# BTS_V2.net
KiCad netlist of a schematic drawn in EAGLE
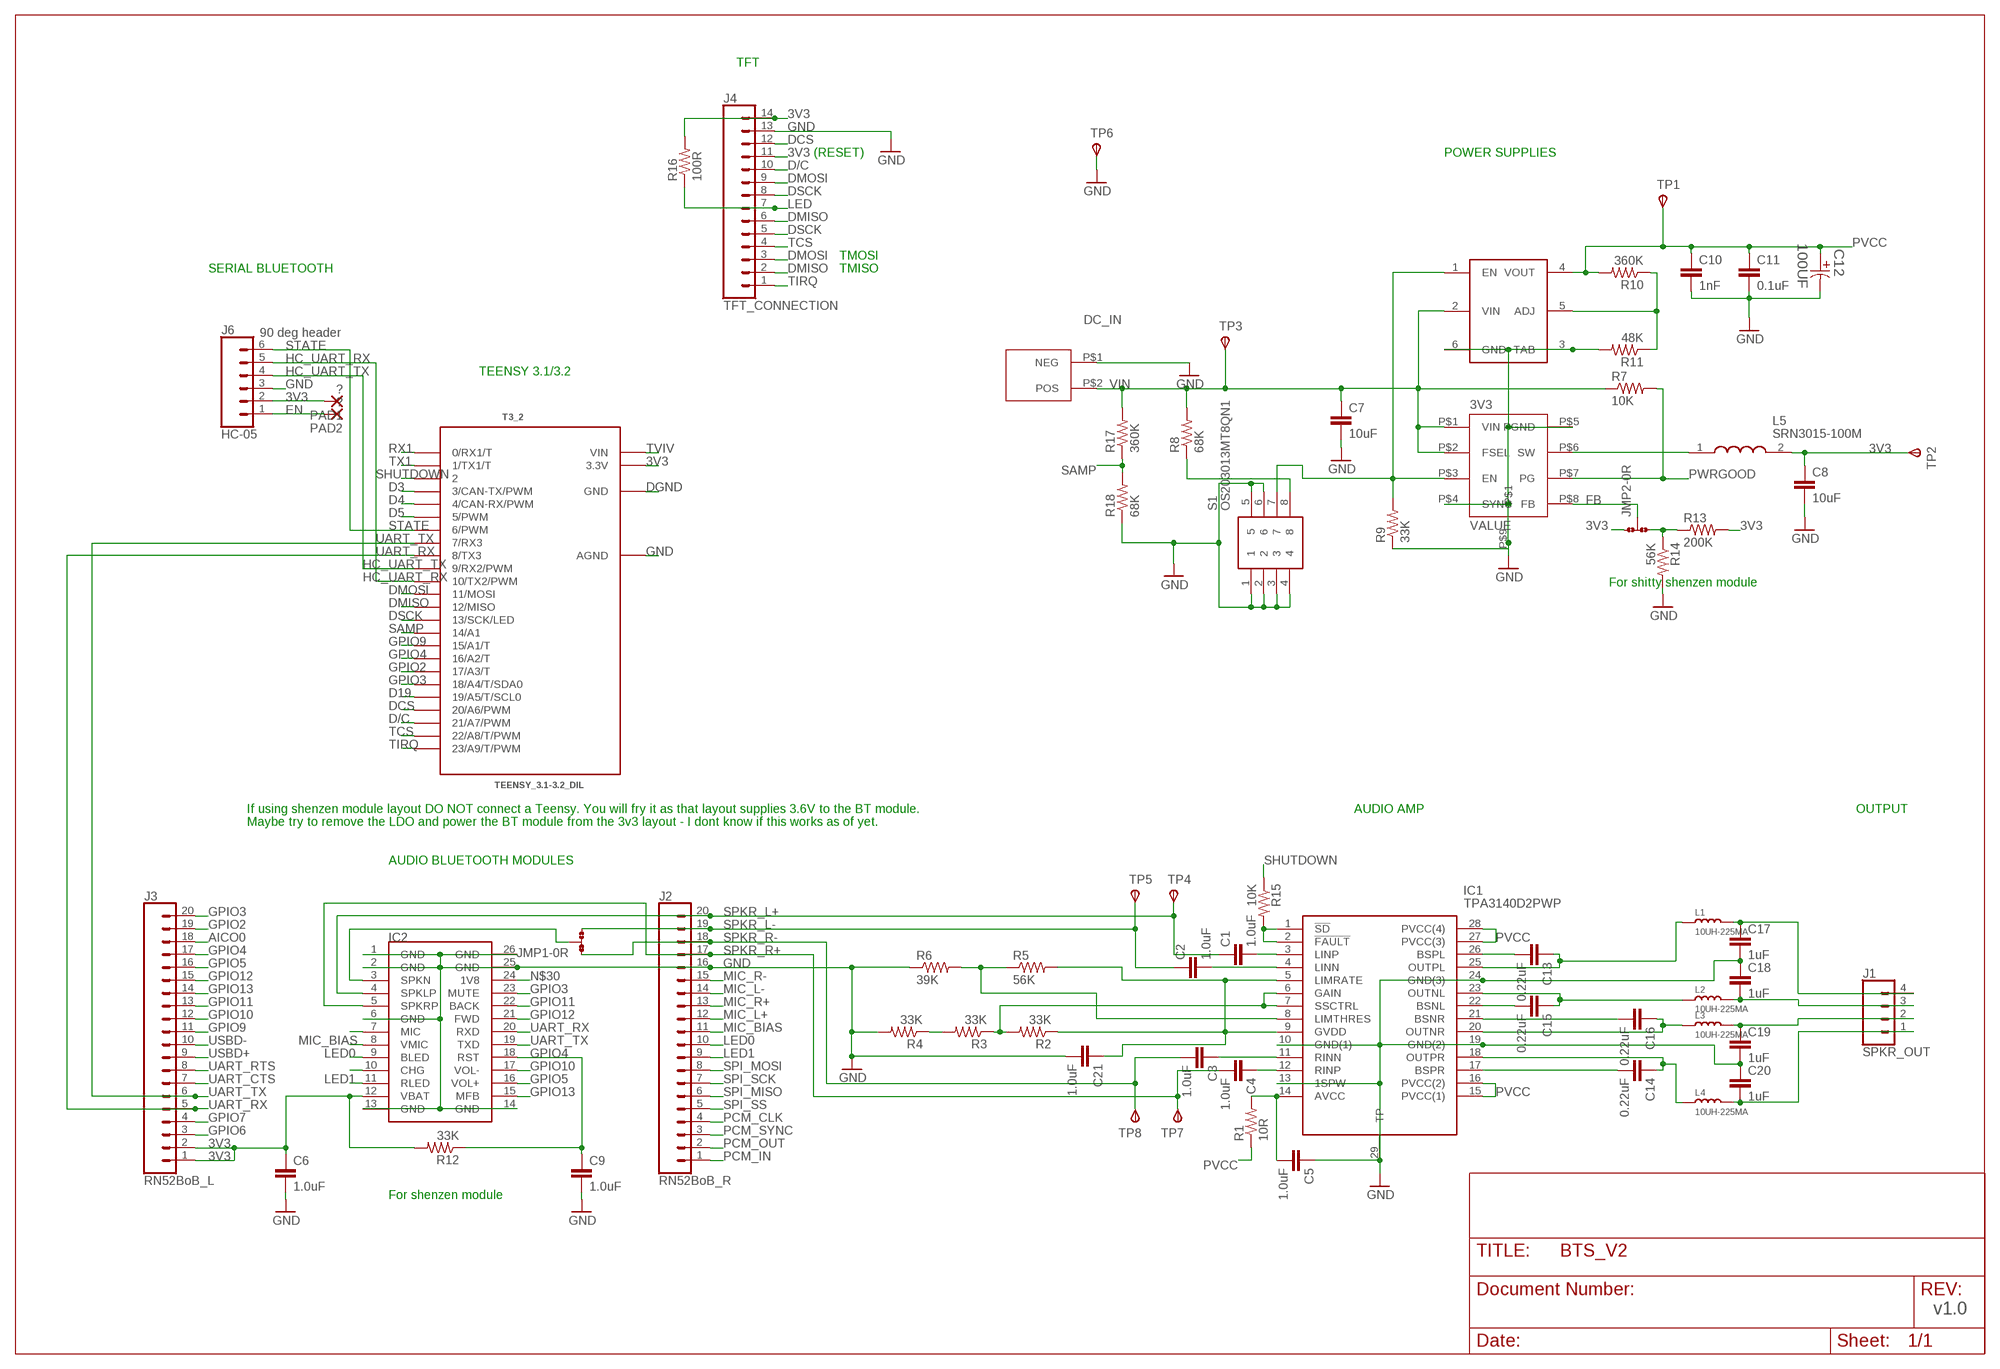
[diagram p0: schematic, sheet 1]

(export (version "E")
  (design (tool "Eeschema 10.0.6"))
  (components
    (comp (ref "3V3")
      (value "ADP2370")
      (footprint "eagle-import:3MM_LFCSP_QFN")
      (libsource (lib "eagle-import") (part "ADP2370"))
    )
    (comp (ref "C1")
      (value "1.0uF")
      (footprint "eagle-import:0603")
      (libsource (lib "eagle-import") (part "1.0UF-0603-16V-10%"))
    )
    (comp (ref "C2")
      (value "1.0uF")
      (footprint "eagle-import:0603")
      (libsource (lib "eagle-import") (part "1.0UF-0603-16V-10%"))
    )
    (comp (ref "C3")
      (value "1.0uF")
      (footprint "eagle-import:0603")
      (libsource (lib "eagle-import") (part "1.0UF-0603-16V-10%"))
    )
    (comp (ref "C4")
      (value "1.0uF")
      (footprint "eagle-import:0603")
      (libsource (lib "eagle-import") (part "1.0UF-0603-16V-10%"))
    )
    (comp (ref "C5")
      (value "1.0uF")
      (footprint "eagle-import:0603")
      (libsource (lib "eagle-import") (part "1.0UF-0603-16V-10%"))
    )
    (comp (ref "C6")
      (value "1.0uF")
      (footprint "eagle-import:0603")
      (libsource (lib "eagle-import") (part "1.0UF-0603-16V-10%"))
    )
    (comp (ref "C7")
      (value "10uF")
      (footprint "eagle-import:C3216")
      (fields (field (name "SPICEPREFIX") "10uF"))
      (libsource (lib "eagle-import") (part "C-EUC3216"))
    )
    (comp (ref "C8")
      (value "10uF")
      (footprint "eagle-import:C3216")
      (libsource (lib "eagle-import") (part "C-EUC3216"))
    )
    (comp (ref "C9")
      (value "1.0uF")
      (footprint "eagle-import:0603")
      (libsource (lib "eagle-import") (part "1.0UF-0603-16V-10%"))
    )
    (comp (ref "C10")
      (value "1nF")
      (footprint "eagle-import:0603")
      (libsource (lib "eagle-import") (part "1.0NF/1000PF-0603-50V-10%"))
    )
    (comp (ref "C11")
      (value "0.1uF")
      (footprint "eagle-import:0603")
      (libsource (lib "eagle-import") (part "0.1UF-0603-25V-(+80/-20%)"))
    )
    (comp (ref "C12")
      (value "100UF")
      (footprint "eagle-import:CAPAE660X610N")
      (fields (field (name "MPN") "EEE-FK1C101P") (field (name "TOLERANCE") "±20 %"))
      (libsource (lib "eagle-import") (part "EEE--CASE-DFK1C101P"))
    )
    (comp (ref "C13")
      (value "0.22uF")
      (footprint "eagle-import:0603")
      (libsource (lib "eagle-import") (part "0.22UF-0603-50V-(-20/+80%)"))
    )
    (comp (ref "C14")
      (value "0.22uF")
      (footprint "eagle-import:0603")
      (libsource (lib "eagle-import") (part "0.22UF-0603-50V-(-20/+80%)"))
    )
    (comp (ref "C15")
      (value "0.22uF")
      (footprint "eagle-import:0603")
      (libsource (lib "eagle-import") (part "0.22UF-0603-50V-(-20/+80%)"))
    )
    (comp (ref "C16")
      (value "0.22uF")
      (footprint "eagle-import:0603")
      (libsource (lib "eagle-import") (part "0.22UF-0603-50V-(-20/+80%)"))
    )
    (comp (ref "C17")
      (value "1uF")
      (footprint "eagle-import:0603")
      (libsource (lib "eagle-import") (part "1.0NF/1000PF-0603-50V-10%"))
    )
    (comp (ref "C18")
      (value "1uF")
      (footprint "eagle-import:0603")
      (libsource (lib "eagle-import") (part "1.0NF/1000PF-0603-50V-10%"))
    )
    (comp (ref "C19")
      (value "1uF")
      (footprint "eagle-import:0603")
      (libsource (lib "eagle-import") (part "1.0NF/1000PF-0603-50V-10%"))
    )
    (comp (ref "C20")
      (value "1uF")
      (footprint "eagle-import:0603")
      (libsource (lib "eagle-import") (part "1.0NF/1000PF-0603-50V-10%"))
    )
    (comp (ref "C21")
      (value "1.0uF")
      (footprint "eagle-import:0603")
      (libsource (lib "eagle-import") (part "1.0UF-0603-16V-10%"))
    )
    (comp (ref "IC1")
      (value "TPA3140D2PWP")
      (footprint "eagle-import:SOP65P640X120-29N")
      (libsource (lib "eagle-import") (part "TPA3140D2PWP"))
    )
    (comp (ref "IC2")
      (value "BLK-MD-SPK-B")
      (footprint "eagle-import:BLK-MD-SPK-B")
      (libsource (lib "eagle-import") (part "BLK-MD-SPK-B"))
    )
    (comp (ref "J1")
      (value "SPKR_OUT")
      (footprint "eagle-import:SCREWTERMINAL-3.5MM-4")
      (libsource (lib "eagle-import") (part "CONN_04SCREW"))
    )
    (comp (ref "J2")
      (value "RN52BoB_R")
      (footprint "eagle-import:1X20")
      (libsource (lib "eagle-import") (part "CONN_20"))
    )
    (comp (ref "J3")
      (value "RN52BoB_L")
      (footprint "eagle-import:1X20")
      (libsource (lib "eagle-import") (part "CONN_20"))
    )
    (comp (ref "J4")
      (value "TFT_CONNECTION")
      (footprint "eagle-import:1X14")
      (libsource (lib "eagle-import") (part "CONN_14"))
    )
    (comp (ref "J6")
      (value "HC-05")
      (footprint "eagle-import:1X06")
      (libsource (lib "eagle-import") (part "CONN_06SILK_FEMALE_PTH"))
    )
    (comp (ref "JMP1")
      (value "0R-JUMPA")
      (footprint "eagle-import:A0R-JMP")
      (libsource (lib "eagle-import") (part "0R-JUMPA"))
    )
    (comp (ref "JMP2")
      (value "0R-JUMPA")
      (footprint "eagle-import:A0R-JMP")
      (libsource (lib "eagle-import") (part "0R-JUMPA"))
    )
    (comp (ref "L1")
      (value "10UH-225MA")
      (footprint "eagle-import:L0806")
      (fields (field (name "MPN") "LQH2MCN100K02L"))
      (libsource (lib "eagle-import") (part "SMD-INDUCTOR-10UH-225MA-10%(0806)"))
    )
    (comp (ref "L2")
      (value "10UH-225MA")
      (footprint "eagle-import:L0806")
      (fields (field (name "MPN") "LQH2MCN100K02L"))
      (libsource (lib "eagle-import") (part "SMD-INDUCTOR-10UH-225MA-10%(0806)"))
    )
    (comp (ref "L3")
      (value "10UH-225MA")
      (footprint "eagle-import:L0806")
      (fields (field (name "MPN") "LQH2MCN100K02L"))
      (libsource (lib "eagle-import") (part "SMD-INDUCTOR-10UH-225MA-10%(0806)"))
    )
    (comp (ref "L4")
      (value "10UH-225MA")
      (footprint "eagle-import:L0806")
      (fields (field (name "MPN") "LQH2MCN100K02L"))
      (libsource (lib "eagle-import") (part "SMD-INDUCTOR-10UH-225MA-10%(0806)"))
    )
    (comp (ref "L5")
      (value "SRN3015-100M")
      (footprint "eagle-import:SRN3015")
      (fields (field (name "RS_PART_NUMBER") "7435071"))
      (libsource (lib "eagle-import") (part "SRN3015-100M"))
    )
    (comp (ref "PAD1")
      (value "?")
      (footprint "eagle-import:SMD1,27-2,54")
      (libsource (lib "eagle-import") (part "SMD2"))
    )
    (comp (ref "PAD2")
      (value "?")
      (footprint "eagle-import:SMD1,27-2,54")
      (libsource (lib "eagle-import") (part "SMD2"))
    )
    (comp (ref "R1")
      (value "10R")
      (footprint "eagle-import:R0603")
      (fields (field (name "RESISTANCE") "10R"))
      (libsource (lib "eagle-import") (part "R-US_R0603"))
    )
    (comp (ref "R2")
      (value "33K")
      (footprint "eagle-import:R0603")
      (fields (field (name "RESISTANCE") "33K"))
      (libsource (lib "eagle-import") (part "R-US_R0603"))
    )
    (comp (ref "R3")
      (value "33K")
      (footprint "eagle-import:R0603")
      (fields (field (name "RESISTANCE") "33K"))
      (libsource (lib "eagle-import") (part "R-US_R0603"))
    )
    (comp (ref "R4")
      (value "33K")
      (footprint "eagle-import:R0603")
      (fields (field (name "RESISTANCE") "33K"))
      (libsource (lib "eagle-import") (part "R-US_R0603"))
    )
    (comp (ref "R5")
      (value "56K")
      (footprint "eagle-import:R0603")
      (fields (field (name "RESISTANCE") "56K"))
      (libsource (lib "eagle-import") (part "R-US_R0603"))
    )
    (comp (ref "R6")
      (value "39K")
      (footprint "eagle-import:R0603")
      (fields (field (name "RESISTANCE") "39K"))
      (libsource (lib "eagle-import") (part "R-US_R0603"))
    )
    (comp (ref "R7")
      (value "10K")
      (footprint "eagle-import:R0603")
      (fields (field (name "RESISTANCE") "10K"))
      (libsource (lib "eagle-import") (part "R-US_R0603"))
    )
    (comp (ref "R8")
      (value "68K")
      (footprint "eagle-import:R0603")
      (fields (field (name "RESISTANCE") "68K"))
      (libsource (lib "eagle-import") (part "R-US_R0603"))
    )
    (comp (ref "R9")
      (value "33K")
      (footprint "eagle-import:R0603")
      (fields (field (name "RESISTANCE") "33K"))
      (libsource (lib "eagle-import") (part "R-US_R0603"))
    )
    (comp (ref "R10")
      (value "360K")
      (footprint "eagle-import:R0603")
      (fields (field (name "RESISTANCE") "10K"))
      (libsource (lib "eagle-import") (part "R-US_R0603"))
    )
    (comp (ref "R11")
      (value "48K")
      (footprint "eagle-import:R0603")
      (fields (field (name "RESISTANCE") "10K"))
      (libsource (lib "eagle-import") (part "R-US_R0603"))
    )
    (comp (ref "R12")
      (value "33K")
      (footprint "eagle-import:R0603")
      (fields (field (name "RESISTANCE") "33K"))
      (libsource (lib "eagle-import") (part "R-US_R0603"))
    )
    (comp (ref "R13")
      (value "200K")
      (footprint "eagle-import:R0603")
      (fields (field (name "RESISTANCE") "10K"))
      (libsource (lib "eagle-import") (part "R-US_R0603"))
    )
    (comp (ref "R14")
      (value "56K")
      (footprint "eagle-import:R0603")
      (fields (field (name "RESISTANCE") "10K"))
      (libsource (lib "eagle-import") (part "R-US_R0603"))
    )
    (comp (ref "R15")
      (value "10K")
      (footprint "eagle-import:R0603")
      (fields (field (name "RESISTANCE") "33K"))
      (libsource (lib "eagle-import") (part "R-US_R0603"))
    )
    (comp (ref "R16")
      (value "100R")
      (footprint "eagle-import:R0603")
      (libsource (lib "eagle-import") (part "R-US_R0603"))
    )
    (comp (ref "R17")
      (value "360K")
      (footprint "eagle-import:R0603")
      (fields (field (name "RESISTANCE") "68K"))
      (libsource (lib "eagle-import") (part "R-US_R0603"))
    )
    (comp (ref "R18")
      (value "68K")
      (footprint "eagle-import:R0603")
      (fields (field (name "RESISTANCE") "68K"))
      (libsource (lib "eagle-import") (part "R-US_R0603"))
    )
    (comp (ref "S1")
      (value "OS203013MT8QN1")
      (footprint "eagle-import:OS203013MT8QN1")
      (libsource (lib "eagle-import") (part "OS203013MT8QN1"))
    )
    (comp (ref "T3_2")
      (value "TEENSY_3.1-3.2_DIL")
      (footprint "eagle-import:TEENSY_3.0-3.2&LC_DIL")
      (libsource (lib "eagle-import") (part "TEENSY_3.1-3.2_DIL"))
    )
    (comp (ref "TP1")
      (value "TPSPAD1-17")
      (footprint "eagle-import:P1-17")
      (libsource (lib "eagle-import") (part "TPSPAD1-17"))
    )
    (comp (ref "TP2")
      (value "TPSPAD1-17")
      (footprint "eagle-import:P1-17")
      (libsource (lib "eagle-import") (part "TPSPAD1-17"))
    )
    (comp (ref "TP3")
      (value "TPSPAD1-17")
      (footprint "eagle-import:P1-17")
      (libsource (lib "eagle-import") (part "TPSPAD1-17"))
    )
    (comp (ref "TP4")
      (value "TPSPAD1-17")
      (footprint "eagle-import:P1-17")
      (libsource (lib "eagle-import") (part "TPSPAD1-17"))
    )
    (comp (ref "TP5")
      (value "TPSPAD1-17")
      (footprint "eagle-import:P1-17")
      (libsource (lib "eagle-import") (part "TPSPAD1-17"))
    )
    (comp (ref "TP6")
      (value "TPSPAD1-17")
      (footprint "eagle-import:P1-17")
      (libsource (lib "eagle-import") (part "TPSPAD1-17"))
    )
    (comp (ref "TP7")
      (value "TPSPAD1-17")
      (footprint "eagle-import:P1-17")
      (libsource (lib "eagle-import") (part "TPSPAD1-17"))
    )
    (comp (ref "TP8")
      (value "TPSPAD1-17")
      (footprint "eagle-import:P1-17")
      (libsource (lib "eagle-import") (part "TPSPAD1-17"))
    )
    (comp (ref "U$1")
      (value "HK_XT-60")
      (footprint "eagle-import:HOBBYKING_XT-60")
      (libsource (lib "eagle-import") (part "HK_XT-60"))
    )
    (comp (ref "U$2")
      (value "NCP59302")
      (footprint "eagle-import:D2PAK-5")
      (libsource (lib "eagle-import") (part "NCP59302"))
    )
  )
  (nets
    (net (code "1") (name "/3V3") (class "Default")
      (node (ref "C6") (pin "1") (pinfunction "1_1") (pintype "passive"))
      (node (ref "C8") (pin "1") (pinfunction "1_1") (pintype "passive"))
      (node (ref "IC2") (pin "12") (pinfunction "VBAT_12") (pintype "bidirectional"))
      (node (ref "J3") (pin "1") (pinfunction "1_1") (pintype "passive"))
      (node (ref "J3") (pin "2") (pinfunction "2_2") (pintype "passive"))
      (node (ref "J4") (pin "11") (pinfunction "11_11") (pintype "passive"))
      (node (ref "J4") (pin "14") (pinfunction "14_14") (pintype "passive"))
      (node (ref "J6") (pin "2") (pinfunction "2_2") (pintype "passive"))
      (node (ref "JMP2") (pin "1") (pinfunction "1_1") (pintype "passive"))
      (node (ref "L5") (pin "2") (pinfunction "2_2") (pintype "input"))
      (node (ref "PAD1") (pin "1") (pinfunction "P_1") (pintype "passive"))
      (node (ref "R12") (pin "2") (pinfunction "2_2") (pintype "passive"))
      (node (ref "R13") (pin "2") (pinfunction "2_2") (pintype "passive"))
      (node (ref "R16") (pin "2") (pinfunction "2_2") (pintype "passive"))
      (node (ref "T3_2") (pin "3.3V") (pinfunction "3.3V_3.3V") (pintype "power_in"))
      (node (ref "TP2") (pin "TP") (pinfunction "PP_TP") (pintype "input"))
    )
    (net (code "2") (name "/AICO0") (class "Default")
      (node (ref "J3") (pin "18") (pinfunction "18_18") (pintype "passive"))
    )
    (net (code "3") (name "/D3") (class "Default")
      (node (ref "T3_2") (pin "3") (pinfunction "3/CAN-TX/PWM_3") (pintype "bidirectional"))
    )
    (net (code "4") (name "/D4") (class "Default")
      (node (ref "T3_2") (pin "4") (pinfunction "4/CAN-RX/PWM_4") (pintype "bidirectional"))
    )
    (net (code "5") (name "/D5") (class "Default")
      (node (ref "T3_2") (pin "5") (pinfunction "5/PWM_5") (pintype "bidirectional"))
    )
    (net (code "6") (name "/D19") (class "Default")
      (node (ref "T3_2") (pin "19/A5") (pinfunction "19/A5/T/SCL0_19/A5") (pintype "bidirectional"))
    )
    (net (code "7") (name "/DCS") (class "Default")
      (node (ref "J4") (pin "12") (pinfunction "12_12") (pintype "passive"))
      (node (ref "T3_2") (pin "20/A6") (pinfunction "20/A6/PWM_20/A6") (pintype "bidirectional"))
    )
    (net (code "8") (name "/DGND") (class "Default")
      (node (ref "T3_2") (pin "GND") (pinfunction "GND_GND") (pintype "power_in"))
    )
    (net (code "9") (name "/DMISO") (class "Default")
      (node (ref "J4") (pin "2") (pinfunction "2_2") (pintype "passive"))
      (node (ref "J4") (pin "6") (pinfunction "6_6") (pintype "passive"))
      (node (ref "T3_2") (pin "12") (pinfunction "12/MISO_12") (pintype "bidirectional"))
    )
    (net (code "10") (name "/DMOSI") (class "Default")
      (node (ref "J4") (pin "3") (pinfunction "3_3") (pintype "passive"))
      (node (ref "J4") (pin "9") (pinfunction "9_9") (pintype "passive"))
      (node (ref "T3_2") (pin "11") (pinfunction "11/MOSI_11") (pintype "bidirectional"))
    )
    (net (code "11") (name "/DSCK") (class "Default")
      (node (ref "J4") (pin "5") (pinfunction "5_5") (pintype "passive"))
      (node (ref "J4") (pin "8") (pinfunction "8_8") (pintype "passive"))
      (node (ref "T3_2") (pin "13") (pinfunction "13/SCK/LED_13") (pintype "bidirectional"))
    )
    (net (code "12") (name "/D{slash}C") (class "Default")
      (node (ref "J4") (pin "10") (pinfunction "10_10") (pintype "passive"))
      (node (ref "T3_2") (pin "21/A7") (pinfunction "21/A7/PWM_21/A7") (pintype "bidirectional"))
    )
    (net (code "13") (name "/EN") (class "Default")
      (node (ref "J6") (pin "1") (pinfunction "1_1") (pintype "passive"))
      (node (ref "PAD2") (pin "1") (pinfunction "P_1") (pintype "passive"))
    )
    (net (code "14") (name "/FB") (class "Default")
      (node (ref "3V3") (pin "P$8") (pinfunction "FB_P$8") (pintype "bidirectional"))
      (node (ref "JMP2") (pin "2") (pinfunction "2_2") (pintype "passive"))
    )
    (net (code "15") (name "/GPIO2") (class "Default")
      (node (ref "J3") (pin "19") (pinfunction "19_19") (pintype "passive"))
      (node (ref "T3_2") (pin "17/A3") (pinfunction "17/A3/T_17/A3") (pintype "bidirectional"))
    )
    (net (code "16") (name "/GPIO3") (class "Default")
      (node (ref "IC2") (pin "23") (pinfunction "MUTE_23") (pintype "bidirectional"))
      (node (ref "J3") (pin "20") (pinfunction "20_20") (pintype "passive"))
      (node (ref "T3_2") (pin "18/A4") (pinfunction "18/A4/T/SDA0_18/A4") (pintype "bidirectional"))
    )
    (net (code "17") (name "/GPIO4") (class "Default")
      (node (ref "C9") (pin "1") (pinfunction "1_1") (pintype "passive"))
      (node (ref "IC2") (pin "18") (pinfunction "RST_18") (pintype "bidirectional"))
      (node (ref "J3") (pin "17") (pinfunction "17_17") (pintype "passive"))
      (node (ref "R12") (pin "1") (pinfunction "1_1") (pintype "passive"))
      (node (ref "T3_2") (pin "16/A2") (pinfunction "16/A2/T_16/A2") (pintype "bidirectional"))
    )
    (net (code "18") (name "/GPIO5") (class "Default")
      (node (ref "IC2") (pin "16") (pinfunction "VOL+_16") (pintype "bidirectional"))
      (node (ref "J3") (pin "16") (pinfunction "16_16") (pintype "passive"))
    )
    (net (code "19") (name "/GPIO6") (class "Default")
      (node (ref "J3") (pin "3") (pinfunction "3_3") (pintype "passive"))
    )
    (net (code "20") (name "/GPIO7") (class "Default")
      (node (ref "J3") (pin "4") (pinfunction "4_4") (pintype "passive"))
    )
    (net (code "21") (name "/GPIO9") (class "Default")
      (node (ref "J3") (pin "11") (pinfunction "11_11") (pintype "passive"))
      (node (ref "T3_2") (pin "15/A1") (pinfunction "15/A1/T_15/A1") (pintype "bidirectional"))
    )
    (net (code "22") (name "/GPIO10") (class "Default")
      (node (ref "IC2") (pin "17") (pinfunction "VOL-_17") (pintype "bidirectional"))
      (node (ref "J3") (pin "12") (pinfunction "12_12") (pintype "passive"))
    )
    (net (code "23") (name "/GPIO11") (class "Default")
      (node (ref "IC2") (pin "22") (pinfunction "BACK_22") (pintype "bidirectional"))
      (node (ref "J3") (pin "13") (pinfunction "13_13") (pintype "passive"))
    )
    (net (code "24") (name "/GPIO12") (class "Default")
      (node (ref "IC2") (pin "21") (pinfunction "FWD_21") (pintype "bidirectional"))
      (node (ref "J3") (pin "15") (pinfunction "15_15") (pintype "passive"))
    )
    (net (code "25") (name "/GPIO13") (class "Default")
      (node (ref "IC2") (pin "15") (pinfunction "MFB_15") (pintype "bidirectional"))
      (node (ref "J3") (pin "14") (pinfunction "14_14") (pintype "passive"))
    )
    (net (code "26") (name "/HC_UART_RX") (class "Default")
      (node (ref "J6") (pin "5") (pinfunction "5_5") (pintype "passive"))
      (node (ref "T3_2") (pin "10") (pinfunction "10/TX2/PWM_10") (pintype "bidirectional"))
    )
    (net (code "27") (name "/HC_UART_TX") (class "Default")
      (node (ref "J6") (pin "4") (pinfunction "4_4") (pintype "passive"))
      (node (ref "T3_2") (pin "9") (pinfunction "9/RX2/PWM_9") (pintype "bidirectional"))
    )
    (net (code "28") (name "/LED") (class "Default")
      (node (ref "J4") (pin "7") (pinfunction "7_7") (pintype "passive"))
      (node (ref "R16") (pin "1") (pinfunction "1_1") (pintype "passive"))
    )
    (net (code "29") (name "/LED0") (class "Default")
      (node (ref "IC2") (pin "9") (pinfunction "BLED_9") (pintype "bidirectional"))
      (node (ref "J2") (pin "10") (pinfunction "10_10") (pintype "passive"))
    )
    (net (code "30") (name "/LED1") (class "Default")
      (node (ref "IC2") (pin "11") (pinfunction "RLED_11") (pintype "bidirectional"))
      (node (ref "J2") (pin "9") (pinfunction "9_9") (pintype "passive"))
    )
    (net (code "31") (name "/MIC_BIAS") (class "Default")
      (node (ref "IC2") (pin "8") (pinfunction "VMIC_8") (pintype "bidirectional"))
      (node (ref "J2") (pin "11") (pinfunction "11_11") (pintype "passive"))
    )
    (net (code "32") (name "/MIC_L+") (class "Default")
      (node (ref "J2") (pin "12") (pinfunction "12_12") (pintype "passive"))
    )
    (net (code "33") (name "/MIC_L-") (class "Default")
      (node (ref "J2") (pin "14") (pinfunction "14_14") (pintype "passive"))
    )
    (net (code "34") (name "/MIC_R+") (class "Default")
      (node (ref "J2") (pin "13") (pinfunction "13_13") (pintype "passive"))
    )
    (net (code "35") (name "/MIC_R-") (class "Default")
      (node (ref "J2") (pin "15") (pinfunction "15_15") (pintype "passive"))
    )
    (net (code "36") (name "/N$30") (class "Default")
      (node (ref "IC2") (pin "24") (pinfunction "1V8_24") (pintype "bidirectional"))
    )
    (net (code "37") (name "/PCM_CLK") (class "Default")
      (node (ref "J2") (pin "4") (pinfunction "4_4") (pintype "passive"))
    )
    (net (code "38") (name "/PCM_IN") (class "Default")
      (node (ref "J2") (pin "1") (pinfunction "1_1") (pintype "passive"))
    )
    (net (code "39") (name "/PCM_OUT") (class "Default")
      (node (ref "J2") (pin "2") (pinfunction "2_2") (pintype "passive"))
    )
    (net (code "40") (name "/PCM_SYNC") (class "Default")
      (node (ref "J2") (pin "3") (pinfunction "3_3") (pintype "passive"))
    )
    (net (code "41") (name "/PVCC") (class "Default")
      (node (ref "C10") (pin "1") (pinfunction "1_1") (pintype "passive"))
      (node (ref "C11") (pin "1") (pinfunction "1_1") (pintype "passive"))
      (node (ref "C12") (pin "1") (pinfunction "1_1") (pintype "passive"))
      (node (ref "IC1") (pin "15") (pinfunction "PVCC(1)_15") (pintype "input"))
      (node (ref "IC1") (pin "16") (pinfunction "PVCC(2)_16") (pintype "input"))
      (node (ref "IC1") (pin "27") (pinfunction "PVCC(3)_27") (pintype "input"))
      (node (ref "IC1") (pin "28") (pinfunction "PVCC(4)_28") (pintype "input"))
      (node (ref "R1") (pin "1") (pinfunction "1_1") (pintype "passive"))
      (node (ref "R10") (pin "2") (pinfunction "2_2") (pintype "passive"))
      (node (ref "TP1") (pin "TP") (pinfunction "PP_TP") (pintype "input"))
      (node (ref "U$2") (pin "4") (pinfunction "VOUT_4") (pintype "bidirectional"))
    )
    (net (code "42") (name "/PWRGOOD") (class "Default")
      (node (ref "3V3") (pin "P$7") (pinfunction "PG_P$7") (pintype "bidirectional"))
      (node (ref "R7") (pin "2") (pinfunction "2_2") (pintype "passive"))
    )
    (net (code "43") (name "/RX1") (class "Default")
      (node (ref "T3_2") (pin "0") (pinfunction "0/RX1/T_0") (pintype "bidirectional"))
    )
    (net (code "44") (name "/SAMP") (class "Default")
      (node (ref "R17") (pin "1") (pinfunction "1_1") (pintype "passive"))
      (node (ref "R18") (pin "2") (pinfunction "2_2") (pintype "passive"))
      (node (ref "T3_2") (pin "14/A0") (pinfunction "14/A1_14/A0") (pintype "bidirectional"))
    )
    (net (code "45") (name "/SHUTDOWN") (class "Default")
      (node (ref "R15") (pin "1") (pinfunction "1_1") (pintype "passive"))
      (node (ref "T3_2") (pin "2") (pinfunction "2_2") (pintype "bidirectional"))
    )
    (net (code "46") (name "/SPI_MISO") (class "Default")
      (node (ref "J2") (pin "6") (pinfunction "6_6") (pintype "passive"))
    )
    (net (code "47") (name "/SPI_MOSI") (class "Default")
      (node (ref "J2") (pin "8") (pinfunction "8_8") (pintype "passive"))
    )
    (net (code "48") (name "/SPI_SCK") (class "Default")
      (node (ref "J2") (pin "7") (pinfunction "7_7") (pintype "passive"))
    )
    (net (code "49") (name "/SPI_SS") (class "Default")
      (node (ref "J2") (pin "5") (pinfunction "5_5") (pintype "passive"))
    )
    (net (code "50") (name "/SPKR_L+") (class "Default")
      (node (ref "C1") (pin "1") (pinfunction "1_1") (pintype "passive"))
      (node (ref "IC2") (pin "4") (pinfunction "SPKLP_4") (pintype "bidirectional"))
      (node (ref "J2") (pin "20") (pinfunction "20_20") (pintype "passive"))
      (node (ref "TP4") (pin "TP") (pinfunction "PP_TP") (pintype "input"))
    )
    (net (code "51") (name "/SPKR_L-") (class "Default")
      (node (ref "C2") (pin "1") (pinfunction "1_1") (pintype "passive"))
      (node (ref "J2") (pin "19") (pinfunction "19_19") (pintype "passive"))
      (node (ref "JMP1") (pin "3") (pinfunction "3_3") (pintype "passive"))
      (node (ref "TP5") (pin "TP") (pinfunction "PP_TP") (pintype "input"))
    )
    (net (code "52") (name "/SPKR_R+") (class "Default")
      (node (ref "C4") (pin "2") (pinfunction "2_2") (pintype "passive"))
      (node (ref "IC2") (pin "5") (pinfunction "SPKRP_5") (pintype "bidirectional"))
      (node (ref "J2") (pin "17") (pinfunction "17_17") (pintype "passive"))
      (node (ref "TP7") (pin "TP") (pinfunction "PP_TP") (pintype "input"))
    )
    (net (code "53") (name "/SPKR_R-") (class "Default")
      (node (ref "C3") (pin "2") (pinfunction "2_2") (pintype "passive"))
      (node (ref "J2") (pin "18") (pinfunction "18_18") (pintype "passive"))
      (node (ref "JMP1") (pin "1") (pinfunction "1_1") (pintype "passive"))
      (node (ref "TP8") (pin "TP") (pinfunction "PP_TP") (pintype "input"))
    )
    (net (code "54") (name "/STATE") (class "Default")
      (node (ref "J6") (pin "6") (pinfunction "6_6") (pintype "passive"))
      (node (ref "T3_2") (pin "6") (pinfunction "6/PWM_6") (pintype "bidirectional"))
    )
    (net (code "55") (name "/TCS") (class "Default")
      (node (ref "J4") (pin "4") (pinfunction "4_4") (pintype "passive"))
      (node (ref "T3_2") (pin "22/A8") (pinfunction "22/A8/T/PWM_22/A8") (pintype "bidirectional"))
    )
    (net (code "56") (name "/TIRQ") (class "Default")
      (node (ref "J4") (pin "1") (pinfunction "1_1") (pintype "passive"))
      (node (ref "T3_2") (pin "23/A9") (pinfunction "23/A9/T/PWM_23/A9") (pintype "bidirectional"))
    )
    (net (code "57") (name "/TVIV") (class "Default")
      (node (ref "T3_2") (pin "VIN") (pinfunction "VIN_VIN") (pintype "power_in"))
    )
    (net (code "58") (name "/TX1") (class "Default")
      (node (ref "T3_2") (pin "1") (pinfunction "1/TX1/T_1") (pintype "bidirectional"))
    )
    (net (code "59") (name "/UART_CTS") (class "Default")
      (node (ref "J3") (pin "7") (pinfunction "7_7") (pintype "passive"))
    )
    (net (code "60") (name "/UART_RTS") (class "Default")
      (node (ref "J3") (pin "8") (pinfunction "8_8") (pintype "passive"))
    )
    (net (code "61") (name "/UART_RX") (class "Default")
      (node (ref "IC2") (pin "20") (pinfunction "RXD_20") (pintype "bidirectional"))
      (node (ref "J3") (pin "5") (pinfunction "5_5") (pintype "passive"))
      (node (ref "T3_2") (pin "8") (pinfunction "8/TX3_8") (pintype "bidirectional"))
    )
    (net (code "62") (name "/UART_TX") (class "Default")
      (node (ref "IC2") (pin "19") (pinfunction "TXD_19") (pintype "bidirectional"))
      (node (ref "J3") (pin "6") (pinfunction "6_6") (pintype "passive"))
      (node (ref "T3_2") (pin "7") (pinfunction "7/RX3_7") (pintype "bidirectional"))
    )
    (net (code "63") (name "/USBD+") (class "Default")
      (node (ref "J3") (pin "9") (pinfunction "9_9") (pintype "passive"))
    )
    (net (code "64") (name "/USBD-") (class "Default")
      (node (ref "J3") (pin "10") (pinfunction "10_10") (pintype "passive"))
    )
    (net (code "65") (name "/VIN") (class "Default")
      (node (ref "3V3") (pin "P$1") (pinfunction "VIN_P$1") (pintype "bidirectional"))
      (node (ref "3V3") (pin "P$2") (pinfunction "FSEL_P$2") (pintype "bidirectional"))
      (node (ref "C7") (pin "1") (pinfunction "1_1") (pintype "passive"))
      (node (ref "R17") (pin "2") (pinfunction "2_2") (pintype "passive"))
      (node (ref "R7") (pin "1") (pinfunction "1_1") (pintype "passive"))
      (node (ref "R8") (pin "2") (pinfunction "2_2") (pintype "passive"))
      (node (ref "TP3") (pin "TP") (pinfunction "PP_TP") (pintype "input"))
      (node (ref "U$1") (pin "P$2") (pinfunction "POS_P$2") (pintype "bidirectional"))
      (node (ref "U$2") (pin "2") (pinfunction "VIN_2") (pintype "bidirectional"))
    )
    (net (code "66") (name "GND") (class "Default")
      (node (ref "3V3") (pin "P$4") (pinfunction "SYNC_P$4") (pintype "bidirectional"))
      (node (ref "3V3") (pin "P$5") (pinfunction "PGND_P$5") (pintype "bidirectional"))
      (node (ref "3V3") (pin "P$9") (pinfunction "P$1_P$9") (pintype "bidirectional"))
      (node (ref "C10") (pin "2") (pinfunction "2_2") (pintype "passive"))
      (node (ref "C11") (pin "2") (pinfunction "2_2") (pintype "passive"))
      (node (ref "C12") (pin "2") (pinfunction "2_2") (pintype "passive"))
      (node (ref "C17") (pin "2") (pinfunction "2_2") (pintype "passive"))
      (node (ref "C18") (pin "1") (pinfunction "1_1") (pintype "passive"))
      (node (ref "C19") (pin "2") (pinfunction "2_2") (pintype "passive"))
      (node (ref "C20") (pin "1") (pinfunction "1_1") (pintype "passive"))
      (node (ref "C21") (pin "2") (pinfunction "2_2") (pintype "passive"))
      (node (ref "C5") (pin "1") (pinfunction "1_1") (pintype "passive"))
      (node (ref "C6") (pin "2") (pinfunction "2_2") (pintype "passive"))
      (node (ref "C7") (pin "2") (pinfunction "2_2") (pintype "passive"))
      (node (ref "C8") (pin "2") (pinfunction "2_2") (pintype "passive"))
      (node (ref "C9") (pin "2") (pinfunction "2_2") (pintype "passive"))
      (node (ref "IC1") (pin "10") (pinfunction "GND(1)_10") (pintype "input"))
      (node (ref "IC1") (pin "13") (pinfunction "1SPW_13") (pintype "input"))
      (node (ref "IC1") (pin "19") (pinfunction "GND(2)_19") (pintype "input"))
      (node (ref "IC1") (pin "24") (pinfunction "GND(3)_24") (pintype "input"))
      (node (ref "IC1") (pin "29") (pinfunction "TP_29") (pintype "input"))
      (node (ref "IC2") (pin "1") (pinfunction "GND_1") (pintype "bidirectional"))
      (node (ref "IC2") (pin "13") (pinfunction "GND_13") (pintype "bidirectional"))
      (node (ref "IC2") (pin "14") (pinfunction "GND_14") (pintype "bidirectional"))
      (node (ref "IC2") (pin "2") (pinfunction "GND_2") (pintype "bidirectional"))
      (node (ref "IC2") (pin "25") (pinfunction "GND_25") (pintype "bidirectional"))
      (node (ref "IC2") (pin "26") (pinfunction "GND_26") (pintype "bidirectional"))
      (node (ref "IC2") (pin "6") (pinfunction "GND_6") (pintype "bidirectional"))
      (node (ref "J2") (pin "16") (pinfunction "16_16") (pintype "passive"))
      (node (ref "J4") (pin "13") (pinfunction "13_13") (pintype "passive"))
      (node (ref "J6") (pin "3") (pinfunction "3_3") (pintype "passive"))
      (node (ref "R11") (pin "2") (pinfunction "2_2") (pintype "passive"))
      (node (ref "R14") (pin "2") (pinfunction "2_2") (pintype "passive"))
      (node (ref "R18") (pin "1") (pinfunction "1_1") (pintype "passive"))
      (node (ref "R4") (pin "2") (pinfunction "2_2") (pintype "passive"))
      (node (ref "R6") (pin "1") (pinfunction "1_1") (pintype "passive"))
      (node (ref "R9") (pin "1") (pinfunction "1_1") (pintype "passive"))
      (node (ref "S1") (pin "1") (pinfunction "1_1") (pintype "input"))
      (node (ref "S1") (pin "2") (pinfunction "2_2") (pintype "input"))
      (node (ref "S1") (pin "3") (pinfunction "3_3") (pintype "input"))
      (node (ref "S1") (pin "4") (pinfunction "4_4") (pintype "input"))
      (node (ref "S1") (pin "5") (pinfunction "5_5") (pintype "input"))
      (node (ref "S1") (pin "6") (pinfunction "6_6") (pintype "input"))
      (node (ref "T3_2") (pin "AGND") (pinfunction "AGND_AGND") (pintype "power_in"))
      (node (ref "TP6") (pin "TP") (pinfunction "PP_TP") (pintype "input"))
      (node (ref "U$1") (pin "P$1") (pinfunction "NEG_P$1") (pintype "bidirectional"))
      (node (ref "U$2") (pin "3") (pinfunction "TAB_3") (pintype "bidirectional"))
      (node (ref "U$2") (pin "6") (pinfunction "GND_6") (pintype "bidirectional"))
    )
    (net (code "67") (name "Net-(3V3-EN)") (class "Default")
      (node (ref "3V3") (pin "P$3") (pinfunction "EN_P$3") (pintype "bidirectional"))
      (node (ref "R9") (pin "2") (pinfunction "2_2") (pintype "passive"))
      (node (ref "S1") (pin "7") (pinfunction "7_7") (pintype "input"))
      (node (ref "U$2") (pin "1") (pinfunction "EN_1") (pintype "bidirectional"))
    )
    (net (code "68") (name "Net-(3V3-SW)") (class "Default")
      (node (ref "3V3") (pin "P$6") (pinfunction "SW_P$6") (pintype "bidirectional"))
      (node (ref "L5") (pin "1") (pinfunction "1_1") (pintype "input"))
    )
    (net (code "69") (name "Net-(C17-Pad1)") (class "Default")
      (node (ref "C17") (pin "1") (pinfunction "1_1") (pintype "passive"))
      (node (ref "J1") (pin "4") (pinfunction "4_4") (pintype "passive"))
      (node (ref "L1") (pin "2") (pinfunction "2_2") (pintype "passive"))
    )
    (net (code "70") (name "Net-(C18-Pad2)") (class "Default")
      (node (ref "C18") (pin "2") (pinfunction "2_2") (pintype "passive"))
      (node (ref "J1") (pin "3") (pinfunction "3_3") (pintype "passive"))
      (node (ref "L2") (pin "2") (pinfunction "2_2") (pintype "passive"))
    )
    (net (code "71") (name "Net-(C19-Pad1)") (class "Default")
      (node (ref "C19") (pin "1") (pinfunction "1_1") (pintype "passive"))
      (node (ref "J1") (pin "2") (pinfunction "2_2") (pintype "passive"))
      (node (ref "L3") (pin "2") (pinfunction "2_2") (pintype "passive"))
    )
    (net (code "72") (name "Net-(C20-Pad2)") (class "Default")
      (node (ref "C20") (pin "2") (pinfunction "2_2") (pintype "passive"))
      (node (ref "J1") (pin "1") (pinfunction "1_1") (pintype "passive"))
      (node (ref "L4") (pin "2") (pinfunction "2_2") (pintype "passive"))
    )
    (net (code "73") (name "Net-(IC1-AVCC)") (class "Default")
      (node (ref "C5") (pin "2") (pinfunction "2_2") (pintype "passive"))
      (node (ref "IC1") (pin "14") (pinfunction "AVCC_14") (pintype "input"))
      (node (ref "R1") (pin "2") (pinfunction "2_2") (pintype "passive"))
    )
    (net (code "74") (name "Net-(IC1-BSNL)") (class "Default")
      (node (ref "C15") (pin "2") (pinfunction "2_2") (pintype "passive"))
      (node (ref "IC1") (pin "22") (pinfunction "BSNL_22") (pintype "input"))
    )
    (net (code "75") (name "Net-(IC1-BSNR)") (class "Default")
      (node (ref "C16") (pin "2") (pinfunction "2_2") (pintype "passive"))
      (node (ref "IC1") (pin "21") (pinfunction "BSNR_21") (pintype "input"))
    )
    (net (code "76") (name "Net-(IC1-BSPL)") (class "Default")
      (node (ref "C13") (pin "2") (pinfunction "2_2") (pintype "passive"))
      (node (ref "IC1") (pin "26") (pinfunction "BSPL_26") (pintype "input"))
    )
    (net (code "77") (name "Net-(IC1-BSPR)") (class "Default")
      (node (ref "C14") (pin "2") (pinfunction "2_2") (pintype "passive"))
      (node (ref "IC1") (pin "17") (pinfunction "BSPR_17") (pintype "input"))
    )
    (net (code "78") (name "Net-(IC1-GAIN)") (class "Default")
      (node (ref "IC1") (pin "6") (pinfunction "GAIN_6") (pintype "input"))
      (node (ref "IC1") (pin "7") (pinfunction "SSCTRL_7") (pintype "input"))
      (node (ref "R2") (pin "2") (pinfunction "2_2") (pintype "passive"))
      (node (ref "R3") (pin "1") (pinfunction "1_1") (pintype "passive"))
    )
    (net (code "79") (name "Net-(IC1-GVDD)") (class "Default")
      (node (ref "C21") (pin "1") (pinfunction "1_1") (pintype "passive"))
      (node (ref "IC1") (pin "5") (pinfunction "LIMRATE_5") (pintype "input"))
      (node (ref "IC1") (pin "9") (pinfunction "GVDD_9") (pintype "input"))
      (node (ref "R2") (pin "1") (pinfunction "1_1") (pintype "passive"))
      (node (ref "R5") (pin "2") (pinfunction "2_2") (pintype "passive"))
    )
    (net (code "80") (name "Net-(IC1-LIMTHRES)") (class "Default")
      (node (ref "IC1") (pin "8") (pinfunction "LIMTHRES_8") (pintype "input"))
      (node (ref "R5") (pin "1") (pinfunction "1_1") (pintype "passive"))
      (node (ref "R6") (pin "2") (pinfunction "2_2") (pintype "passive"))
    )
    (net (code "81") (name "Net-(IC1-LINN)") (class "Default")
      (node (ref "C2") (pin "2") (pinfunction "2_2") (pintype "passive"))
      (node (ref "IC1") (pin "4") (pinfunction "LINN_4") (pintype "input"))
    )
    (net (code "82") (name "Net-(IC1-LINP)") (class "Default")
      (node (ref "C1") (pin "2") (pinfunction "2_2") (pintype "passive"))
      (node (ref "IC1") (pin "3") (pinfunction "LINP_3") (pintype "input"))
    )
    (net (code "83") (name "Net-(IC1-OUTNL)") (class "Default")
      (node (ref "C15") (pin "1") (pinfunction "1_1") (pintype "passive"))
      (node (ref "IC1") (pin "23") (pinfunction "OUTNL_23") (pintype "input"))
      (node (ref "L2") (pin "1") (pinfunction "1_1") (pintype "passive"))
    )
    (net (code "84") (name "Net-(IC1-OUTNR)") (class "Default")
      (node (ref "C16") (pin "1") (pinfunction "1_1") (pintype "passive"))
      (node (ref "IC1") (pin "20") (pinfunction "OUTNR_20") (pintype "input"))
      (node (ref "L3") (pin "1") (pinfunction "1_1") (pintype "passive"))
    )
    (net (code "85") (name "Net-(IC1-OUTPL)") (class "Default")
      (node (ref "C13") (pin "1") (pinfunction "1_1") (pintype "passive"))
      (node (ref "IC1") (pin "25") (pinfunction "OUTPL_25") (pintype "input"))
      (node (ref "L1") (pin "1") (pinfunction "1_1") (pintype "passive"))
    )
    (net (code "86") (name "Net-(IC1-OUTPR)") (class "Default")
      (node (ref "C14") (pin "1") (pinfunction "1_1") (pintype "passive"))
      (node (ref "IC1") (pin "18") (pinfunction "OUTPR_18") (pintype "input"))
      (node (ref "L4") (pin "1") (pinfunction "1_1") (pintype "passive"))
    )
    (net (code "87") (name "Net-(IC1-RINN)") (class "Default")
      (node (ref "C3") (pin "1") (pinfunction "1_1") (pintype "passive"))
      (node (ref "IC1") (pin "11") (pinfunction "RINN_11") (pintype "input"))
    )
    (net (code "88") (name "Net-(IC1-RINP)") (class "Default")
      (node (ref "C4") (pin "1") (pinfunction "1_1") (pintype "passive"))
      (node (ref "IC1") (pin "12") (pinfunction "RINP_12") (pintype "input"))
    )
    (net (code "89") (name "Net-(IC1-~{FAULT})") (class "Default")
      (node (ref "IC1") (pin "1") (pinfunction "~{SD}_1") (pintype "input"))
      (node (ref "IC1") (pin "2") (pinfunction "~{FAULT}_2") (pintype "input"))
      (node (ref "R15") (pin "2") (pinfunction "2_2") (pintype "passive"))
    )
    (net (code "90") (name "Net-(IC2-SPKN)") (class "Default")
      (node (ref "IC2") (pin "3") (pinfunction "SPKN_3") (pintype "bidirectional"))
      (node (ref "JMP1") (pin "2") (pinfunction "2_2") (pintype "passive"))
    )
    (net (code "91") (name "Net-(JMP2-Pad3)") (class "Default")
      (node (ref "JMP2") (pin "3") (pinfunction "3_3") (pintype "passive"))
      (node (ref "R13") (pin "1") (pinfunction "1_1") (pintype "passive"))
      (node (ref "R14") (pin "1") (pinfunction "1_1") (pintype "passive"))
    )
    (net (code "92") (name "Net-(R3-Pad2)") (class "Default")
      (node (ref "R3") (pin "2") (pinfunction "2_2") (pintype "passive"))
      (node (ref "R4") (pin "1") (pinfunction "1_1") (pintype "passive"))
    )
    (net (code "93") (name "Net-(R8-Pad1)") (class "Default")
      (node (ref "R8") (pin "1") (pinfunction "1_1") (pintype "passive"))
      (node (ref "S1") (pin "8") (pinfunction "8_8") (pintype "input"))
    )
    (net (code "94") (name "Net-(U$2-ADJ)") (class "Default")
      (node (ref "R10") (pin "1") (pinfunction "1_1") (pintype "passive"))
      (node (ref "R11") (pin "1") (pinfunction "1_1") (pintype "passive"))
      (node (ref "U$2") (pin "5") (pinfunction "ADJ_5") (pintype "bidirectional"))
    )
    (net (code "95") (name "unconnected-(IC2-CHG-Pad10)") (class "Default")
      (node (ref "IC2") (pin "10") (pinfunction "CHG_10") (pintype "bidirectional"))
    )
    (net (code "96") (name "unconnected-(IC2-MIC-Pad7)") (class "Default")
      (node (ref "IC2") (pin "7") (pinfunction "MIC_7") (pintype "bidirectional"))
    )
  )
)
